# Driver.net
KiCad netlist of a schematic drawn in Altium Designer
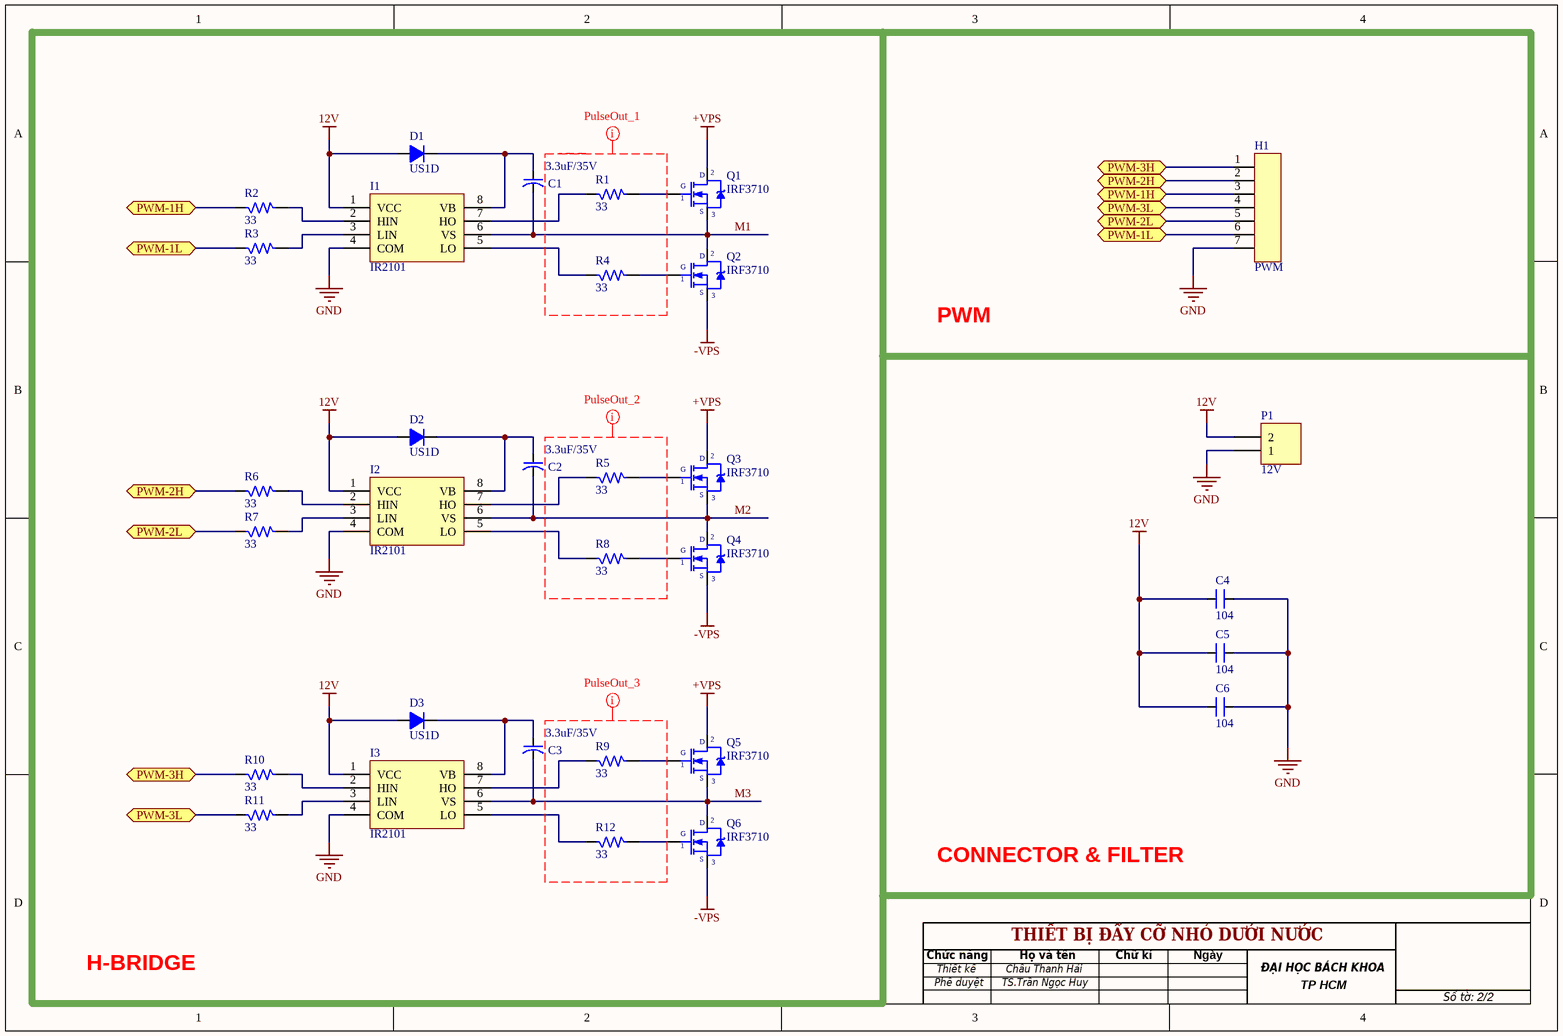
[diagram p0: Driver.SchDoc]

(export (version "E")
  (design (tool "Eeschema 10.0.6"))
  (components
    (comp (ref "C1")
      (value "3.3uF/35V")
      (footprint "3.3uF/35V Bootstrap")
      (libsource (lib "BLDC_Libraries") (part "3.3uF/35V"))
    )
    (comp (ref "C2")
      (value "3.3uF/35V")
      (footprint "3.3uF/35V Bootstrap")
      (libsource (lib "BLDC_Libraries") (part "3.3uF/35V"))
    )
    (comp (ref "C3")
      (value "3.3uF/35V")
      (footprint "3.3uF/35V Bootstrap")
      (libsource (lib "BLDC_Libraries") (part "3.3uF/35V"))
    )
    (comp (ref "C4")
      (value "104")
      (footprint "Non-Capacitor 104 SMD")
      (libsource (lib "BLDC_Libraries") (part "104"))
    )
    (comp (ref "C5")
      (value "104")
      (footprint "Non-Capacitor 104 SMD")
      (libsource (lib "BLDC_Libraries") (part "104"))
    )
    (comp (ref "C6")
      (value "104")
      (footprint "Non-Capacitor 104 SMD")
      (libsource (lib "BLDC_Libraries") (part "104"))
    )
    (comp (ref "D1")
      (value "US1D")
      (footprint "BLDC_Libraries:US1D")
      (libsource (lib "BLDC_Libraries") (part "US1D"))
    )
    (comp (ref "D2")
      (value "US1D")
      (footprint "BLDC_Libraries:US1D")
      (libsource (lib "BLDC_Libraries") (part "US1D"))
    )
    (comp (ref "D3")
      (value "US1D")
      (footprint "BLDC_Libraries:US1D")
      (libsource (lib "BLDC_Libraries") (part "US1D"))
    )
    (comp (ref "H1")
      (value "PWM")
      (footprint "Header 7 Male")
      (libsource (lib "BLDC_Libraries") (part "Header 7x1"))
    )
    (comp (ref "I1")
      (value "IR2101")
      (footprint "IR2101S")
      (libsource (lib "BLDC_Libraries") (part "IR2101"))
    )
    (comp (ref "I2")
      (value "IR2101")
      (footprint "IR2101S")
      (libsource (lib "BLDC_Libraries") (part "IR2101"))
    )
    (comp (ref "I3")
      (value "IR2101")
      (footprint "IR2101S")
      (libsource (lib "BLDC_Libraries") (part "IR2101"))
    )
    (comp (ref "P1")
      (value "12V")
      (footprint "HDR1X2")
      (description "Header, 2-Pin")
      (fields (field (name "PUBLISHER") "Altium Limited"))
      (libsource (lib "NBBLib 14-03-2012") (part "Header 2"))
    )
    (comp (ref "Q1")
      (value "IRF3710")
      (footprint "IRF3710")
      (libsource (lib "BLDC_Libraries") (part "IRF3710"))
    )
    (comp (ref "Q2")
      (value "IRF3710")
      (footprint "IRF3710")
      (libsource (lib "BLDC_Libraries") (part "IRF3710"))
    )
    (comp (ref "Q3")
      (value "IRF3710")
      (footprint "IRF3710")
      (libsource (lib "BLDC_Libraries") (part "IRF3710"))
    )
    (comp (ref "Q4")
      (value "IRF3710")
      (footprint "IRF3710")
      (libsource (lib "BLDC_Libraries") (part "IRF3710"))
    )
    (comp (ref "Q5")
      (value "IRF3710")
      (footprint "IRF3710")
      (libsource (lib "BLDC_Libraries") (part "IRF3710"))
    )
    (comp (ref "Q6")
      (value "IRF3710")
      (footprint "IRF3710")
      (libsource (lib "BLDC_Libraries") (part "IRF3710"))
    )
    (comp (ref "R1")
      (value "33")
      (footprint "Resistor SMD 0603")
      (libsource (lib "BLDC_Libraries") (part "Resistors"))
    )
    (comp (ref "R2")
      (value "33")
      (footprint "Resistor SMD 0603")
      (libsource (lib "BLDC_Libraries") (part "Resistors"))
    )
    (comp (ref "R3")
      (value "33")
      (footprint "Resistor SMD 0603")
      (libsource (lib "BLDC_Libraries") (part "Resistors"))
    )
    (comp (ref "R4")
      (value "33")
      (footprint "Resistor SMD 0603")
      (libsource (lib "BLDC_Libraries") (part "Resistors"))
    )
    (comp (ref "R5")
      (value "33")
      (footprint "Resistor SMD 0603")
      (libsource (lib "BLDC_Libraries") (part "Resistors"))
    )
    (comp (ref "R6")
      (value "33")
      (footprint "Resistor SMD 0603")
      (libsource (lib "BLDC_Libraries") (part "Resistors"))
    )
    (comp (ref "R7")
      (value "33")
      (footprint "Resistor SMD 0603")
      (libsource (lib "BLDC_Libraries") (part "Resistors"))
    )
    (comp (ref "R8")
      (value "33")
      (footprint "Resistor SMD 0603")
      (libsource (lib "BLDC_Libraries") (part "Resistors"))
    )
    (comp (ref "R9")
      (value "33")
      (footprint "Resistor SMD 0603")
      (libsource (lib "BLDC_Libraries") (part "Resistors"))
    )
    (comp (ref "R10")
      (value "33")
      (footprint "Resistor SMD 0603")
      (libsource (lib "BLDC_Libraries") (part "Resistors"))
    )
    (comp (ref "R11")
      (value "33")
      (footprint "Resistor SMD 0603")
      (libsource (lib "BLDC_Libraries") (part "Resistors"))
    )
    (comp (ref "R12")
      (value "33")
      (footprint "Resistor SMD 0603")
      (libsource (lib "BLDC_Libraries") (part "Resistors"))
    )
  )
  (nets
    (net (code "1") (name "+VPS") (class "Default")
      (node (ref "Q1") (pin "2") (pinfunction "D_2") (pintype "passive"))
      (node (ref "Q3") (pin "2") (pinfunction "D_2") (pintype "passive"))
      (node (ref "Q5") (pin "2") (pinfunction "D_2") (pintype "passive"))
    )
    (net (code "2") (name "-VPS") (class "Default")
      (node (ref "Q2") (pin "3") (pinfunction "S_3") (pintype "passive"))
      (node (ref "Q4") (pin "3") (pinfunction "S_3") (pintype "passive"))
      (node (ref "Q6") (pin "3") (pinfunction "S_3") (pintype "passive"))
    )
    (net (code "3") (name "/M1") (class "Default")
      (node (ref "C1") (pin "2") (pinfunction "2_2") (pintype "passive"))
      (node (ref "I1") (pin "6") (pinfunction "VS_6") (pintype "passive"))
      (node (ref "Q1") (pin "3") (pinfunction "S_3") (pintype "passive"))
      (node (ref "Q2") (pin "2") (pinfunction "D_2") (pintype "passive"))
    )
    (net (code "4") (name "/M2") (class "Default")
      (node (ref "C2") (pin "2") (pinfunction "2_2") (pintype "passive"))
      (node (ref "I2") (pin "6") (pinfunction "VS_6") (pintype "passive"))
      (node (ref "Q3") (pin "3") (pinfunction "S_3") (pintype "passive"))
      (node (ref "Q4") (pin "2") (pinfunction "D_2") (pintype "passive"))
    )
    (net (code "5") (name "/M3") (class "Default")
      (node (ref "C3") (pin "2") (pinfunction "2_2") (pintype "passive"))
      (node (ref "I3") (pin "6") (pinfunction "VS_6") (pintype "passive"))
      (node (ref "Q5") (pin "3") (pinfunction "S_3") (pintype "passive"))
      (node (ref "Q6") (pin "2") (pinfunction "D_2") (pintype "passive"))
    )
    (net (code "6") (name "/PWM-1H") (class "Default")
      (node (ref "H1") (pin "3") (pinfunction "3_3") (pintype "passive"))
      (node (ref "R2") (pin "1") (pinfunction "1_1") (pintype "passive"))
    )
    (net (code "7") (name "/PWM-1L") (class "Default")
      (node (ref "H1") (pin "6") (pinfunction "6_6") (pintype "passive"))
      (node (ref "R3") (pin "1") (pinfunction "1_1") (pintype "passive"))
    )
    (net (code "8") (name "/PWM-2H") (class "Default")
      (node (ref "H1") (pin "2") (pinfunction "2_2") (pintype "passive"))
      (node (ref "R6") (pin "1") (pinfunction "1_1") (pintype "passive"))
    )
    (net (code "9") (name "/PWM-2L") (class "Default")
      (node (ref "H1") (pin "5") (pinfunction "5_5") (pintype "passive"))
      (node (ref "R7") (pin "1") (pinfunction "1_1") (pintype "passive"))
    )
    (net (code "10") (name "/PWM-3H") (class "Default")
      (node (ref "H1") (pin "1") (pinfunction "1_1") (pintype "passive"))
      (node (ref "R10") (pin "1") (pinfunction "1_1") (pintype "passive"))
    )
    (net (code "11") (name "/PWM-3L") (class "Default")
      (node (ref "H1") (pin "4") (pinfunction "4_4") (pintype "passive"))
      (node (ref "R11") (pin "1") (pinfunction "1_1") (pintype "passive"))
    )
    (net (code "12") (name "12V") (class "Default")
      (node (ref "C4") (pin "1") (pinfunction "1_1") (pintype "passive"))
      (node (ref "C5") (pin "1") (pinfunction "1_1") (pintype "passive"))
      (node (ref "C6") (pin "1") (pinfunction "1_1") (pintype "passive"))
      (node (ref "D1") (pin "2") (pinfunction "A_2") (pintype "passive"))
      (node (ref "D2") (pin "2") (pinfunction "A_2") (pintype "passive"))
      (node (ref "D3") (pin "2") (pinfunction "A_2") (pintype "passive"))
      (node (ref "I1") (pin "1") (pinfunction "VCC_1") (pintype "passive"))
      (node (ref "I2") (pin "1") (pinfunction "VCC_1") (pintype "passive"))
      (node (ref "I3") (pin "1") (pinfunction "VCC_1") (pintype "passive"))
      (node (ref "P1") (pin "2") (pinfunction "2_2") (pintype "passive"))
    )
    (net (code "13") (name "GND") (class "Default")
      (node (ref "C4") (pin "2") (pinfunction "2_2") (pintype "passive"))
      (node (ref "C5") (pin "2") (pinfunction "2_2") (pintype "passive"))
      (node (ref "C6") (pin "2") (pinfunction "2_2") (pintype "passive"))
      (node (ref "H1") (pin "7") (pinfunction "7_7") (pintype "passive"))
      (node (ref "I1") (pin "4") (pinfunction "COM_4") (pintype "passive"))
      (node (ref "I2") (pin "4") (pinfunction "COM_4") (pintype "passive"))
      (node (ref "I3") (pin "4") (pinfunction "COM_4") (pintype "passive"))
      (node (ref "P1") (pin "1") (pinfunction "1_1") (pintype "passive"))
    )
    (net (code "14") (name "Net-(D1-K)") (class "Default")
      (node (ref "C1") (pin "1") (pinfunction "1_1") (pintype "passive"))
      (node (ref "D1") (pin "1") (pinfunction "K_1") (pintype "passive"))
      (node (ref "I1") (pin "8") (pinfunction "VB_8") (pintype "passive"))
    )
    (net (code "15") (name "Net-(D2-K)") (class "Default")
      (node (ref "C2") (pin "1") (pinfunction "1_1") (pintype "passive"))
      (node (ref "D2") (pin "1") (pinfunction "K_1") (pintype "passive"))
      (node (ref "I2") (pin "8") (pinfunction "VB_8") (pintype "passive"))
    )
    (net (code "16") (name "Net-(D3-K)") (class "Default")
      (node (ref "C3") (pin "1") (pinfunction "1_1") (pintype "passive"))
      (node (ref "D3") (pin "1") (pinfunction "K_1") (pintype "passive"))
      (node (ref "I3") (pin "8") (pinfunction "VB_8") (pintype "passive"))
    )
    (net (code "17") (name "Net-(I1-HIN)") (class "Default")
      (node (ref "I1") (pin "2") (pinfunction "HIN_2") (pintype "passive"))
      (node (ref "R2") (pin "2") (pinfunction "2_2") (pintype "passive"))
    )
    (net (code "18") (name "Net-(I1-HO)") (class "Default")
      (node (ref "I1") (pin "7") (pinfunction "HO_7") (pintype "passive"))
      (node (ref "R1") (pin "1") (pinfunction "1_1") (pintype "passive"))
    )
    (net (code "19") (name "Net-(I1-LIN)") (class "Default")
      (node (ref "I1") (pin "3") (pinfunction "LIN_3") (pintype "passive"))
      (node (ref "R3") (pin "2") (pinfunction "2_2") (pintype "passive"))
    )
    (net (code "20") (name "Net-(I1-LO)") (class "Default")
      (node (ref "I1") (pin "5") (pinfunction "LO_5") (pintype "passive"))
      (node (ref "R4") (pin "1") (pinfunction "1_1") (pintype "passive"))
    )
    (net (code "21") (name "Net-(I2-HIN)") (class "Default")
      (node (ref "I2") (pin "2") (pinfunction "HIN_2") (pintype "passive"))
      (node (ref "R6") (pin "2") (pinfunction "2_2") (pintype "passive"))
    )
    (net (code "22") (name "Net-(I2-HO)") (class "Default")
      (node (ref "I2") (pin "7") (pinfunction "HO_7") (pintype "passive"))
      (node (ref "R5") (pin "1") (pinfunction "1_1") (pintype "passive"))
    )
    (net (code "23") (name "Net-(I2-LIN)") (class "Default")
      (node (ref "I2") (pin "3") (pinfunction "LIN_3") (pintype "passive"))
      (node (ref "R7") (pin "2") (pinfunction "2_2") (pintype "passive"))
    )
    (net (code "24") (name "Net-(I2-LO)") (class "Default")
      (node (ref "I2") (pin "5") (pinfunction "LO_5") (pintype "passive"))
      (node (ref "R8") (pin "1") (pinfunction "1_1") (pintype "passive"))
    )
    (net (code "25") (name "Net-(I3-HIN)") (class "Default")
      (node (ref "I3") (pin "2") (pinfunction "HIN_2") (pintype "passive"))
      (node (ref "R10") (pin "2") (pinfunction "2_2") (pintype "passive"))
    )
    (net (code "26") (name "Net-(I3-HO)") (class "Default")
      (node (ref "I3") (pin "7") (pinfunction "HO_7") (pintype "passive"))
      (node (ref "R9") (pin "1") (pinfunction "1_1") (pintype "passive"))
    )
    (net (code "27") (name "Net-(I3-LIN)") (class "Default")
      (node (ref "I3") (pin "3") (pinfunction "LIN_3") (pintype "passive"))
      (node (ref "R11") (pin "2") (pinfunction "2_2") (pintype "passive"))
    )
    (net (code "28") (name "Net-(I3-LO)") (class "Default")
      (node (ref "I3") (pin "5") (pinfunction "LO_5") (pintype "passive"))
      (node (ref "R12") (pin "1") (pinfunction "1_1") (pintype "passive"))
    )
    (net (code "29") (name "Net-(Q1-G)") (class "Default")
      (node (ref "Q1") (pin "1") (pinfunction "G_1") (pintype "passive"))
      (node (ref "R1") (pin "2") (pinfunction "2_2") (pintype "passive"))
    )
    (net (code "30") (name "Net-(Q2-G)") (class "Default")
      (node (ref "Q2") (pin "1") (pinfunction "G_1") (pintype "passive"))
      (node (ref "R4") (pin "2") (pinfunction "2_2") (pintype "passive"))
    )
    (net (code "31") (name "Net-(Q3-G)") (class "Default")
      (node (ref "Q3") (pin "1") (pinfunction "G_1") (pintype "passive"))
      (node (ref "R5") (pin "2") (pinfunction "2_2") (pintype "passive"))
    )
    (net (code "32") (name "Net-(Q4-G)") (class "Default")
      (node (ref "Q4") (pin "1") (pinfunction "G_1") (pintype "passive"))
      (node (ref "R8") (pin "2") (pinfunction "2_2") (pintype "passive"))
    )
    (net (code "33") (name "Net-(Q5-G)") (class "Default")
      (node (ref "Q5") (pin "1") (pinfunction "G_1") (pintype "passive"))
      (node (ref "R9") (pin "2") (pinfunction "2_2") (pintype "passive"))
    )
    (net (code "34") (name "Net-(Q6-G)") (class "Default")
      (node (ref "Q6") (pin "1") (pinfunction "G_1") (pintype "passive"))
      (node (ref "R12") (pin "2") (pinfunction "2_2") (pintype "passive"))
    )
  )
)
